# mainboard.net
KiCad netlist of a schematic drawn in EAGLE
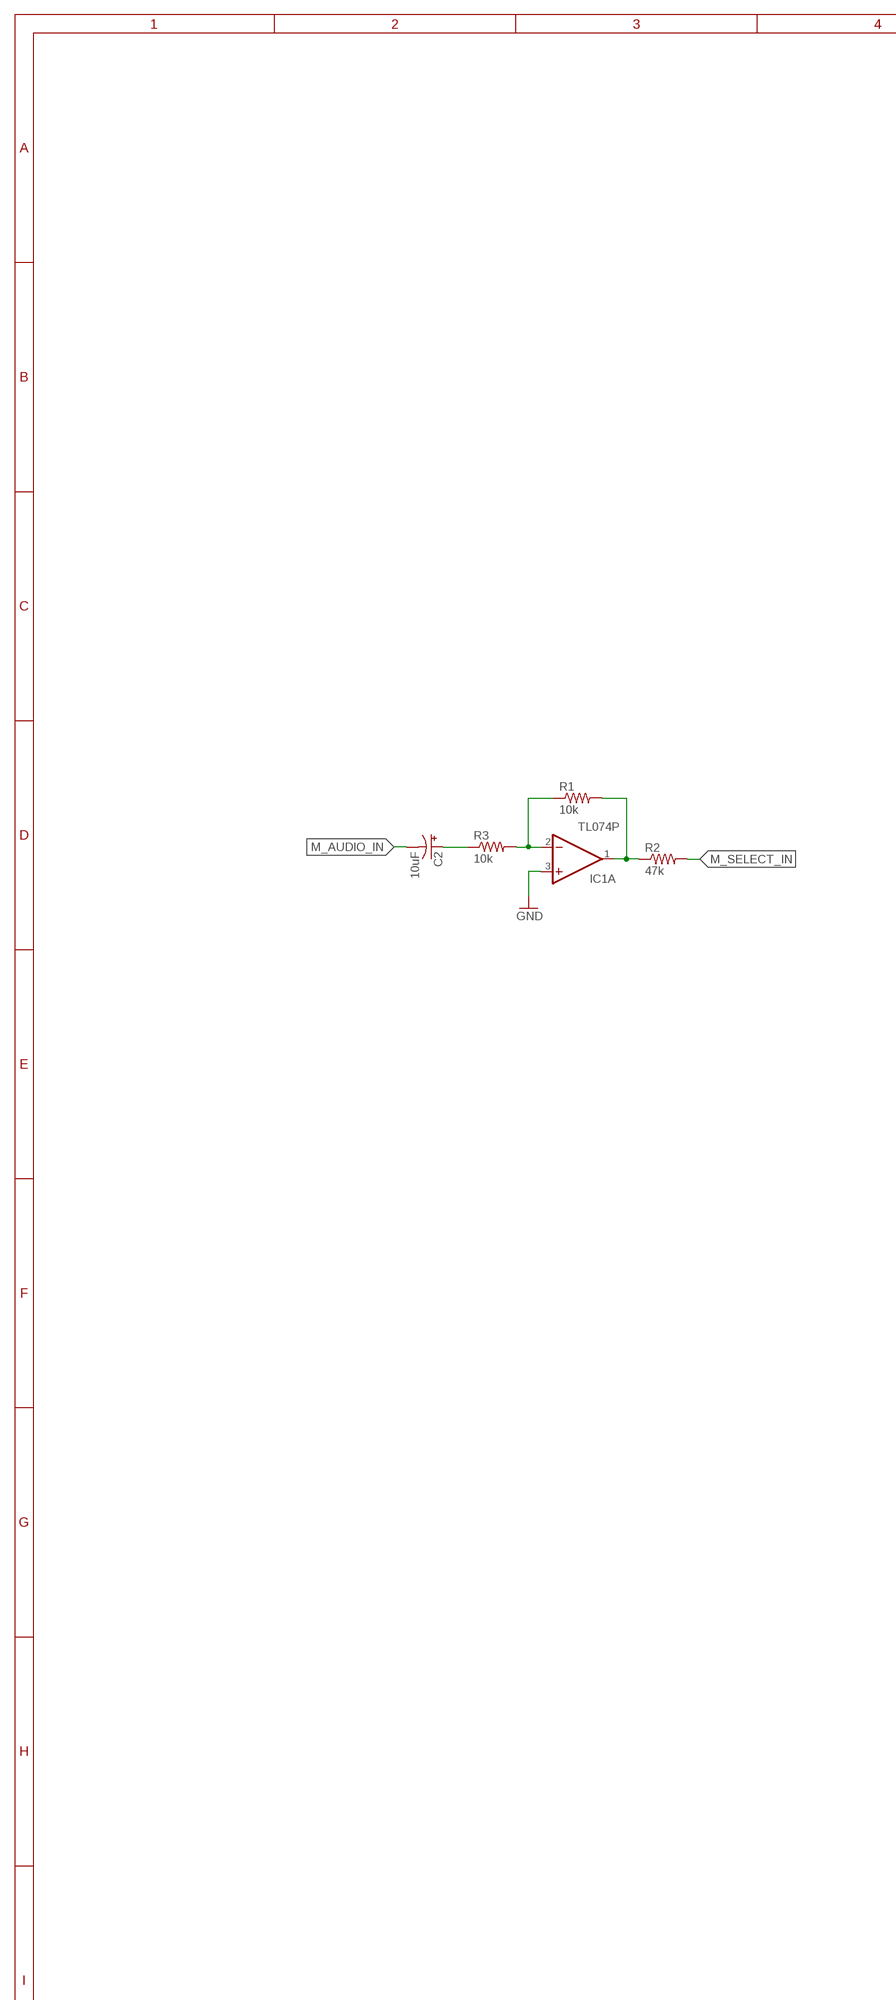
[diagram p0: schematic, sheet 1, part 1 of 2]
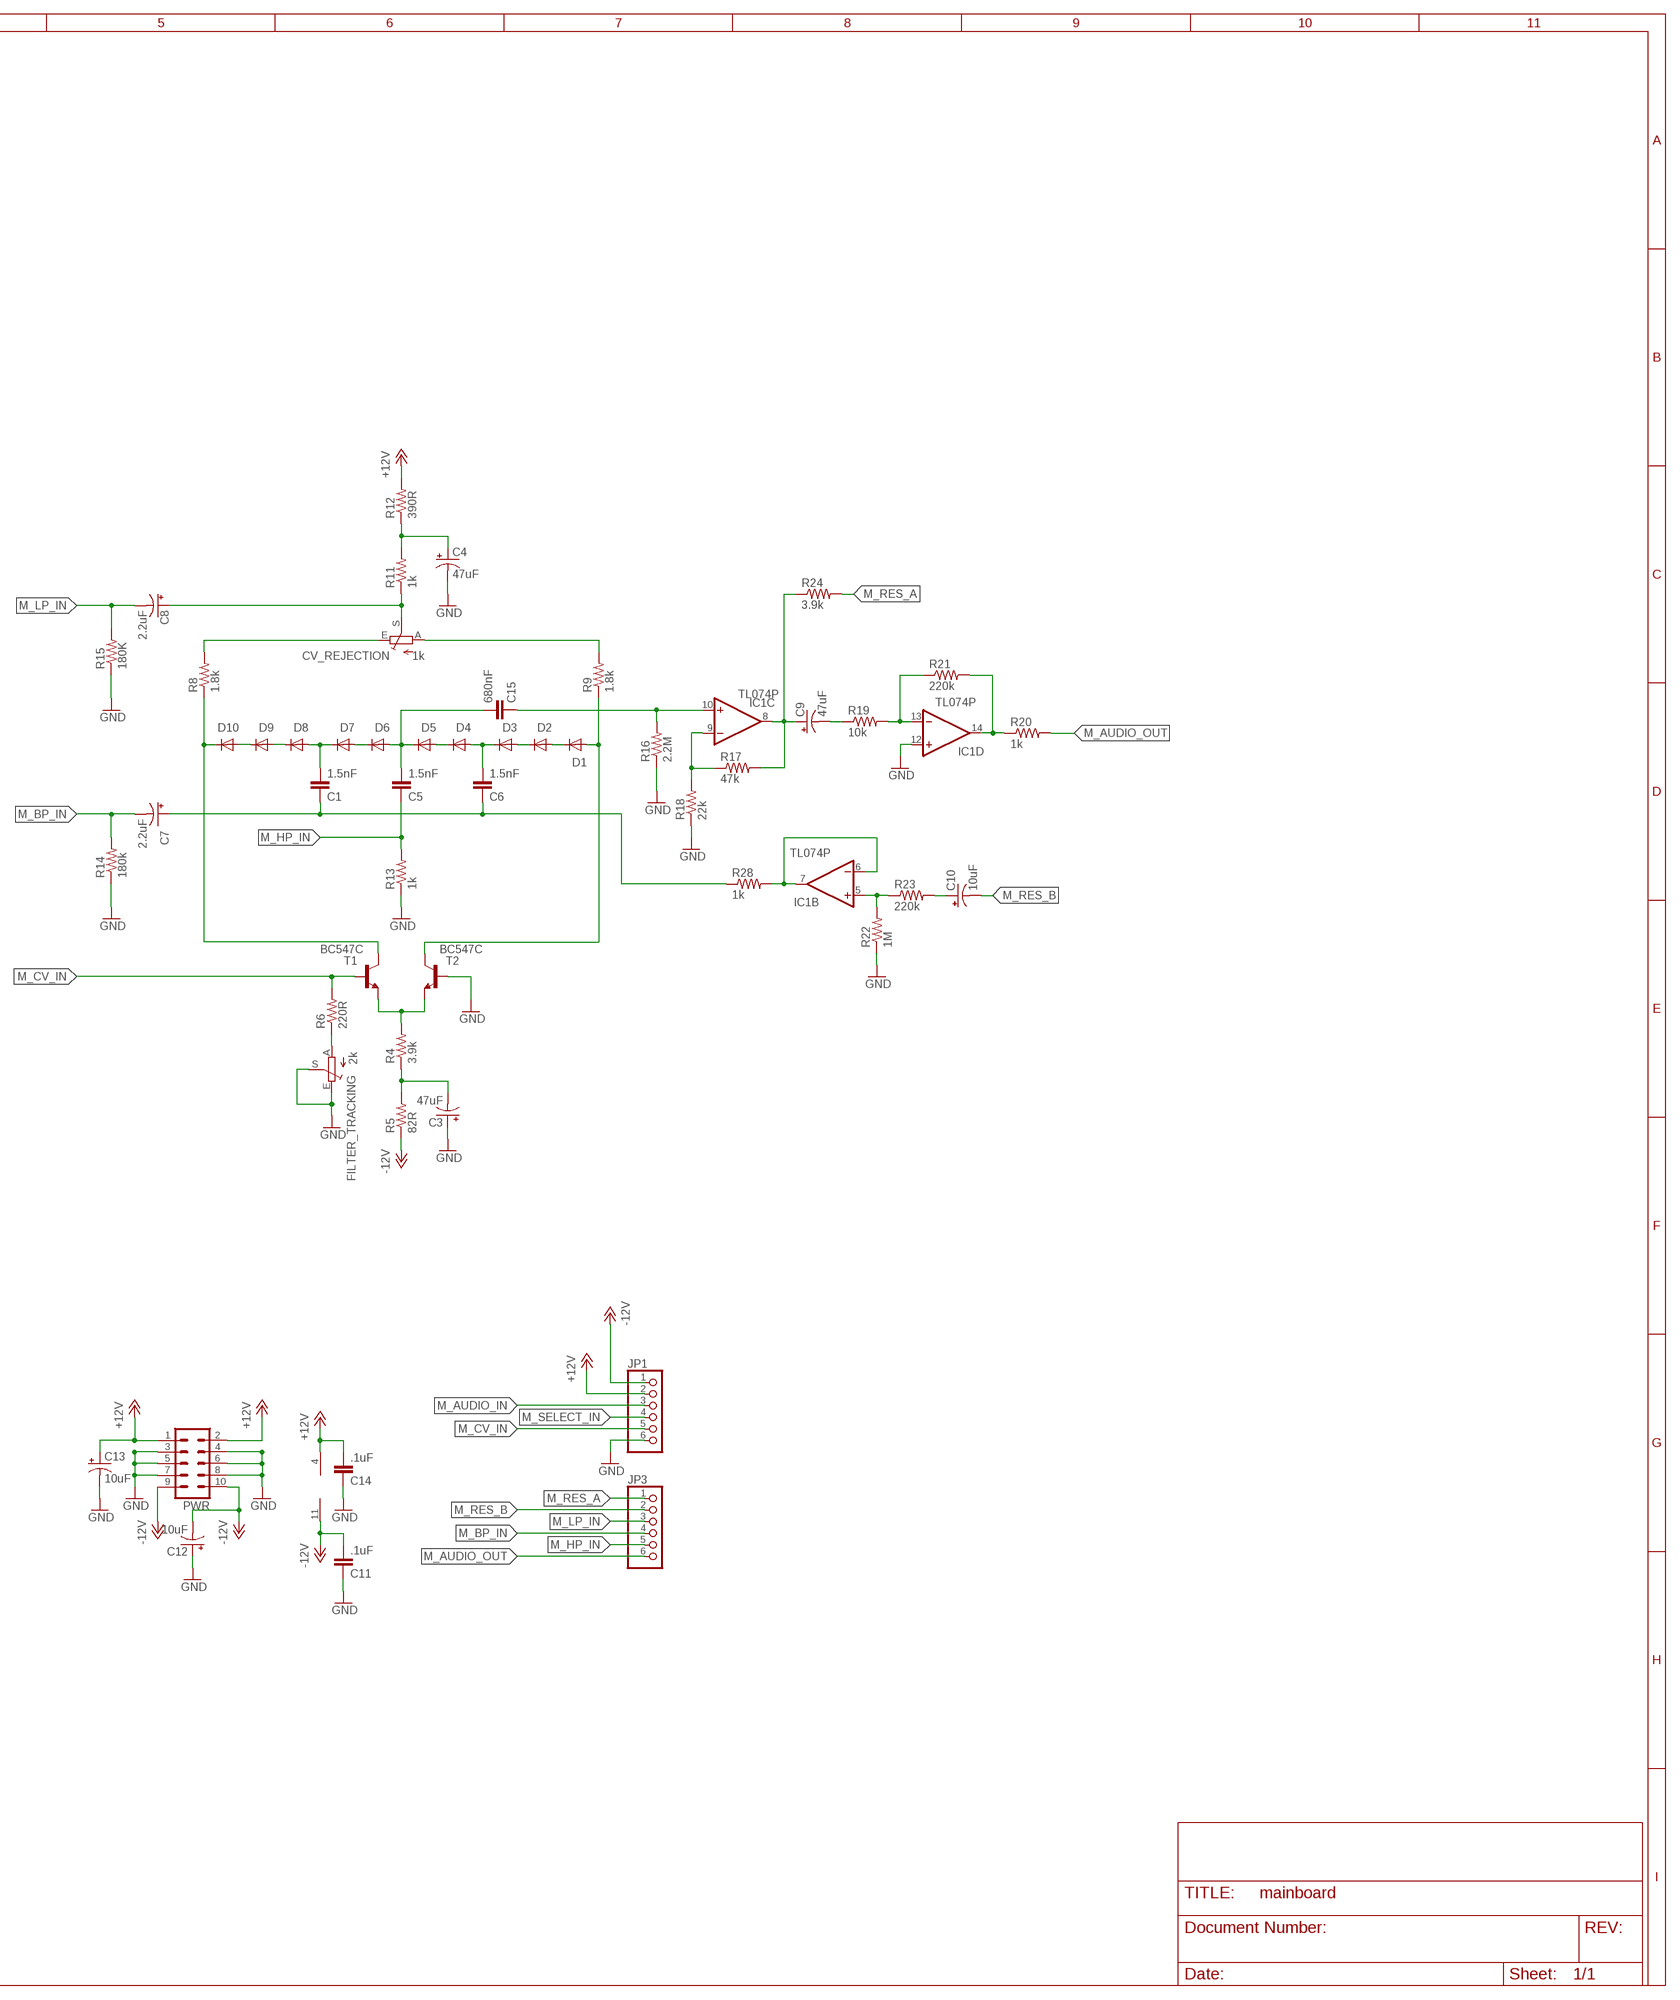
[diagram p1: schematic, sheet 1, part 2 of 2]

(export (version "E")
  (design (tool "Eeschema 10.0.6"))
  (components
    (comp (ref "C1")
      (value "1.5nF")
      (footprint "eagle-import:C050-024X044")
      (libsource (lib "eagle-import") (part "C-EU050-024X044"))
    )
    (comp (ref "C2")
      (value "10uF")
      (footprint "eagle-import:E2,5-5")
      (libsource (lib "eagle-import") (part "CPOL-USE2.5-5"))
    )
    (comp (ref "C3")
      (value "47uF")
      (footprint "eagle-import:E2,5-5")
      (libsource (lib "eagle-import") (part "CPOL-USE2.5-5"))
    )
    (comp (ref "C4")
      (value "47uF")
      (footprint "eagle-import:E2,5-5")
      (libsource (lib "eagle-import") (part "CPOL-USE2.5-5"))
    )
    (comp (ref "C5")
      (value "1.5nF")
      (footprint "eagle-import:C050-024X044")
      (libsource (lib "eagle-import") (part "C-EU050-024X044"))
    )
    (comp (ref "C6")
      (value "1.5nF")
      (footprint "eagle-import:C050-024X044")
      (libsource (lib "eagle-import") (part "C-EU050-024X044"))
    )
    (comp (ref "C7")
      (value "2.2uF")
      (footprint "eagle-import:E2,5-5")
      (libsource (lib "eagle-import") (part "CPOL-USE2.5-5"))
    )
    (comp (ref "C8")
      (value "2.2uF")
      (footprint "eagle-import:E2,5-5")
      (libsource (lib "eagle-import") (part "CPOL-USE2.5-5"))
    )
    (comp (ref "C9")
      (value "47uF")
      (footprint "eagle-import:E2,5-5")
      (libsource (lib "eagle-import") (part "CPOL-USE2.5-5"))
    )
    (comp (ref "C10")
      (value "10uF")
      (footprint "eagle-import:E2,5-5")
      (libsource (lib "eagle-import") (part "CPOL-USE2.5-5"))
    )
    (comp (ref "C11")
      (value ".1uF")
      (footprint "eagle-import:C050-024X044")
      (libsource (lib "eagle-import") (part "C-EU050-024X044"))
    )
    (comp (ref "C12")
      (value "10uF")
      (footprint "eagle-import:E2,5-5")
      (libsource (lib "eagle-import") (part "CPOL-USE2.5-5"))
    )
    (comp (ref "C13")
      (value "10uF")
      (footprint "eagle-import:E2,5-5")
      (libsource (lib "eagle-import") (part "CPOL-USE2.5-5"))
    )
    (comp (ref "C14")
      (value ".1uF")
      (footprint "eagle-import:C050-024X044")
      (libsource (lib "eagle-import") (part "C-EU050-024X044"))
    )
    (comp (ref "C15")
      (value "680nF")
      (footprint "eagle-import:C050-035X075")
      (libsource (lib "eagle-import") (part "resistor_348_C-EU050-035X075"))
    )
    (comp (ref "CV_REJECTION")
      (value "1k")
      (footprint "eagle-import:S64YW")
      (libsource (lib "eagle-import") (part "TRIM_1234-S64YW"))
    )
    (comp (ref "D1")
      (value "1N4148DO35-7")
      (footprint "eagle-import:DO35-7")
      (libsource (lib "eagle-import") (part "1N4148DO35-7"))
    )
    (comp (ref "D2")
      (value "1N4148DO35-7")
      (footprint "eagle-import:DO35-7")
      (libsource (lib "eagle-import") (part "1N4148DO35-7"))
    )
    (comp (ref "D3")
      (value "1N4148DO35-7")
      (footprint "eagle-import:DO35-7")
      (libsource (lib "eagle-import") (part "1N4148DO35-7"))
    )
    (comp (ref "D4")
      (value "1N4148DO35-7")
      (footprint "eagle-import:DO35-7")
      (libsource (lib "eagle-import") (part "1N4148DO35-7"))
    )
    (comp (ref "D5")
      (value "1N4148DO35-7")
      (footprint "eagle-import:DO35-7")
      (libsource (lib "eagle-import") (part "1N4148DO35-7"))
    )
    (comp (ref "D6")
      (value "1N4148DO35-7")
      (footprint "eagle-import:DO35-7")
      (libsource (lib "eagle-import") (part "1N4148DO35-7"))
    )
    (comp (ref "D7")
      (value "1N4148DO35-7")
      (footprint "eagle-import:DO35-7")
      (libsource (lib "eagle-import") (part "1N4148DO35-7"))
    )
    (comp (ref "D8")
      (value "1N4148DO35-7")
      (footprint "eagle-import:DO35-7")
      (libsource (lib "eagle-import") (part "1N4148DO35-7"))
    )
    (comp (ref "D9")
      (value "1N4148DO35-7")
      (footprint "eagle-import:DO35-7")
      (libsource (lib "eagle-import") (part "1N4148DO35-7"))
    )
    (comp (ref "D10")
      (value "1N4148DO35-7")
      (footprint "eagle-import:DO35-7")
      (libsource (lib "eagle-import") (part "1N4148DO35-7"))
    )
    (comp (ref "FILTER_TRACKING")
      (value "2k")
      (footprint "eagle-import:S64YW")
      (libsource (lib "eagle-import") (part "TRIM_1234-S64YW"))
    )
    (comp (ref "IC1")
      (value "TL074P")
      (footprint "eagle-import:DIL14")
      (libsource (lib "eagle-import") (part "TL074P"))
    )
    (comp (ref "JP1")
      (value "PINHD-1X6")
      (footprint "eagle-import:1X06")
      (libsource (lib "eagle-import") (part "PINHD-1X6"))
    )
    (comp (ref "JP3")
      (value "PINHD-1X6")
      (footprint "eagle-import:1X06")
      (libsource (lib "eagle-import") (part "PINHD-1X6"))
    )
    (comp (ref "PWR")
      (value "ML10")
      (footprint "eagle-import:ML10")
      (libsource (lib "eagle-import") (part "ML10"))
    )
    (comp (ref "R1")
      (value "10k")
      (footprint "eagle-import:0204_7")
      (libsource (lib "eagle-import") (part "R-US_0204/7"))
    )
    (comp (ref "R2")
      (value "47k")
      (footprint "eagle-import:0204_7")
      (libsource (lib "eagle-import") (part "R-US_0204/7"))
    )
    (comp (ref "R3")
      (value "10k")
      (footprint "eagle-import:0204_7")
      (libsource (lib "eagle-import") (part "R-US_0204/7"))
    )
    (comp (ref "R4")
      (value "3.9k")
      (footprint "eagle-import:0204_7")
      (libsource (lib "eagle-import") (part "R-US_0204/7"))
    )
    (comp (ref "R5")
      (value "82R")
      (footprint "eagle-import:0204_7")
      (libsource (lib "eagle-import") (part "R-US_0204/7"))
    )
    (comp (ref "R6")
      (value "220R")
      (footprint "eagle-import:0204_7")
      (libsource (lib "eagle-import") (part "R-US_0204/7"))
    )
    (comp (ref "R8")
      (value "1.8k")
      (footprint "eagle-import:0204_7")
      (libsource (lib "eagle-import") (part "R-US_0204/7"))
    )
    (comp (ref "R9")
      (value "1.8k")
      (footprint "eagle-import:0204_7")
      (libsource (lib "eagle-import") (part "R-US_0204/7"))
    )
    (comp (ref "R11")
      (value "1k")
      (footprint "eagle-import:0204_7")
      (libsource (lib "eagle-import") (part "R-US_0204/7"))
    )
    (comp (ref "R12")
      (value "390R")
      (footprint "eagle-import:0204_7")
      (libsource (lib "eagle-import") (part "R-US_0204/7"))
    )
    (comp (ref "R13")
      (value "1k")
      (footprint "eagle-import:0204_7")
      (libsource (lib "eagle-import") (part "R-US_0204/7"))
    )
    (comp (ref "R14")
      (value "180k")
      (footprint "eagle-import:0204_7")
      (libsource (lib "eagle-import") (part "R-US_0204/7"))
    )
    (comp (ref "R15")
      (value "180K")
      (footprint "eagle-import:0204_7")
      (libsource (lib "eagle-import") (part "R-US_0204/7"))
    )
    (comp (ref "R16")
      (value "2.2M")
      (footprint "eagle-import:0204_7")
      (libsource (lib "eagle-import") (part "R-US_0204/7"))
    )
    (comp (ref "R17")
      (value "47k")
      (footprint "eagle-import:0204_7")
      (libsource (lib "eagle-import") (part "R-US_0204/7"))
    )
    (comp (ref "R18")
      (value "22k")
      (footprint "eagle-import:0204_7")
      (libsource (lib "eagle-import") (part "R-US_0204/7"))
    )
    (comp (ref "R19")
      (value "10k")
      (footprint "eagle-import:0204_7")
      (libsource (lib "eagle-import") (part "R-US_0204/7"))
    )
    (comp (ref "R20")
      (value "1k")
      (footprint "eagle-import:0204_7")
      (libsource (lib "eagle-import") (part "R-US_0204/7"))
    )
    (comp (ref "R21")
      (value "220k")
      (footprint "eagle-import:0204_7")
      (libsource (lib "eagle-import") (part "R-US_0204/7"))
    )
    (comp (ref "R22")
      (value "1M")
      (footprint "eagle-import:0204_7")
      (libsource (lib "eagle-import") (part "R-US_0204/7"))
    )
    (comp (ref "R23")
      (value "220k")
      (footprint "eagle-import:0204_7")
      (libsource (lib "eagle-import") (part "R-US_0204/7"))
    )
    (comp (ref "R24")
      (value "3.9k")
      (footprint "eagle-import:0204_7")
      (libsource (lib "eagle-import") (part "R-US_0204/7"))
    )
    (comp (ref "R28")
      (value "1k")
      (footprint "eagle-import:0204_7")
      (libsource (lib "eagle-import") (part "R-US_0204/7"))
    )
    (comp (ref "T1")
      (value "BC547C")
      (footprint "eagle-import:TO92-CBE")
      (libsource (lib "eagle-import") (part "-NPN-TO92-CBEBC547"))
    )
    (comp (ref "T2")
      (value "BC547C")
      (footprint "eagle-import:TO92-CBE")
      (libsource (lib "eagle-import") (part "-NPN-TO92-CBEBC547"))
    )
  )
  (nets
    (net (code "1") (name "+12V") (class "Default")
      (node (ref "C13") (pin "+") (pinfunction "+_+") (pintype "passive"))
      (node (ref "C14") (pin "1") (pinfunction "1_1") (pintype "passive"))
      (node (ref "IC1") (pin "4") (pinfunction "V+_4") (pintype "power_in"))
      (node (ref "JP1") (pin "2") (pinfunction "2_2") (pintype "passive"))
      (node (ref "PWR") (pin "1") (pinfunction "1_1") (pintype "passive"))
      (node (ref "PWR") (pin "2") (pinfunction "2_2") (pintype "passive"))
      (node (ref "R12") (pin "2") (pinfunction "2_2") (pintype "passive"))
    )
    (net (code "2") (name "-12V") (class "Default")
      (node (ref "C11") (pin "1") (pinfunction "1_1") (pintype "passive"))
      (node (ref "C12") (pin "-") (pinfunction "-_-") (pintype "passive"))
      (node (ref "IC1") (pin "11") (pinfunction "V-_11") (pintype "power_in"))
      (node (ref "JP1") (pin "1") (pinfunction "1_1") (pintype "passive"))
      (node (ref "PWR") (pin "10") (pinfunction "10_10") (pintype "passive"))
      (node (ref "PWR") (pin "9") (pinfunction "9_9") (pintype "passive"))
      (node (ref "R5") (pin "1") (pinfunction "1_1") (pintype "passive"))
    )
    (net (code "3") (name "GND") (class "Default")
      (node (ref "C11") (pin "2") (pinfunction "2_2") (pintype "passive"))
      (node (ref "C12") (pin "+") (pinfunction "+_+") (pintype "passive"))
      (node (ref "C13") (pin "-") (pinfunction "-_-") (pintype "passive"))
      (node (ref "C14") (pin "2") (pinfunction "2_2") (pintype "passive"))
      (node (ref "C3") (pin "+") (pinfunction "+_+") (pintype "passive"))
      (node (ref "C4") (pin "-") (pinfunction "-_-") (pintype "passive"))
      (node (ref "FILTER_TRACKING") (pin "E") (pinfunction "E_E") (pintype "passive"))
      (node (ref "FILTER_TRACKING") (pin "S") (pinfunction "S_S") (pintype "passive"))
      (node (ref "IC1") (pin "12") (pinfunction "+IN_12") (pintype "input"))
      (node (ref "IC1") (pin "3") (pinfunction "+IN_3") (pintype "input"))
      (node (ref "JP1") (pin "6") (pinfunction "6_6") (pintype "passive"))
      (node (ref "PWR") (pin "3") (pinfunction "3_3") (pintype "passive"))
      (node (ref "PWR") (pin "4") (pinfunction "4_4") (pintype "passive"))
      (node (ref "PWR") (pin "5") (pinfunction "5_5") (pintype "passive"))
      (node (ref "PWR") (pin "6") (pinfunction "6_6") (pintype "passive"))
      (node (ref "PWR") (pin "7") (pinfunction "7_7") (pintype "passive"))
      (node (ref "PWR") (pin "8") (pinfunction "8_8") (pintype "passive"))
      (node (ref "R13") (pin "1") (pinfunction "1_1") (pintype "passive"))
      (node (ref "R14") (pin "1") (pinfunction "1_1") (pintype "passive"))
      (node (ref "R15") (pin "1") (pinfunction "1_1") (pintype "passive"))
      (node (ref "R16") (pin "1") (pinfunction "1_1") (pintype "passive"))
      (node (ref "R18") (pin "1") (pinfunction "1_1") (pintype "passive"))
      (node (ref "R22") (pin "1") (pinfunction "1_1") (pintype "passive"))
      (node (ref "T2") (pin "B") (pinfunction "B_B") (pintype "passive"))
    )
    (net (code "4") (name "M_AUDIO_IN") (class "Default")
      (node (ref "C2") (pin "-") (pinfunction "-_-") (pintype "passive"))
      (node (ref "JP1") (pin "3") (pinfunction "3_3") (pintype "passive"))
    )
    (net (code "5") (name "M_AUDIO_OUT") (class "Default")
      (node (ref "JP3") (pin "6") (pinfunction "6_6") (pintype "passive"))
      (node (ref "R20") (pin "2") (pinfunction "2_2") (pintype "passive"))
    )
    (net (code "6") (name "M_BP_IN") (class "Default")
      (node (ref "C7") (pin "-") (pinfunction "-_-") (pintype "passive"))
      (node (ref "JP3") (pin "4") (pinfunction "4_4") (pintype "passive"))
      (node (ref "R14") (pin "2") (pinfunction "2_2") (pintype "passive"))
    )
    (net (code "7") (name "M_CV_IN") (class "Default")
      (node (ref "JP1") (pin "5") (pinfunction "5_5") (pintype "passive"))
      (node (ref "R6") (pin "2") (pinfunction "2_2") (pintype "passive"))
      (node (ref "T1") (pin "B") (pinfunction "B_B") (pintype "passive"))
    )
    (net (code "8") (name "M_HP_IN") (class "Default")
      (node (ref "C5") (pin "2") (pinfunction "2_2") (pintype "passive"))
      (node (ref "JP3") (pin "5") (pinfunction "5_5") (pintype "passive"))
      (node (ref "R13") (pin "2") (pinfunction "2_2") (pintype "passive"))
    )
    (net (code "9") (name "M_LP_IN") (class "Default")
      (node (ref "C8") (pin "-") (pinfunction "-_-") (pintype "passive"))
      (node (ref "JP3") (pin "3") (pinfunction "3_3") (pintype "passive"))
      (node (ref "R15") (pin "2") (pinfunction "2_2") (pintype "passive"))
    )
    (net (code "10") (name "M_RES_A") (class "Default")
      (node (ref "JP3") (pin "1") (pinfunction "1_1") (pintype "passive"))
      (node (ref "R24") (pin "2") (pinfunction "2_2") (pintype "passive"))
    )
    (net (code "11") (name "M_RES_B") (class "Default")
      (node (ref "C10") (pin "-") (pinfunction "-_-") (pintype "passive"))
      (node (ref "JP3") (pin "2") (pinfunction "2_2") (pintype "passive"))
    )
    (net (code "12") (name "M_SELECT_IN") (class "Default")
      (node (ref "JP1") (pin "4") (pinfunction "4_4") (pintype "passive"))
      (node (ref "R2") (pin "2") (pinfunction "2_2") (pintype "passive"))
    )
    (net (code "13") (name "Net-(C1-Pad1)") (class "Default")
      (node (ref "C1") (pin "1") (pinfunction "1_1") (pintype "passive"))
      (node (ref "D7") (pin "C") (pinfunction "C_C") (pintype "passive"))
      (node (ref "D8") (pin "A") (pinfunction "A_A") (pintype "passive"))
    )
    (net (code "14") (name "Net-(C1-Pad2)") (class "Default")
      (node (ref "C1") (pin "2") (pinfunction "2_2") (pintype "passive"))
      (node (ref "C6") (pin "2") (pinfunction "2_2") (pintype "passive"))
      (node (ref "C7") (pin "+") (pinfunction "+_+") (pintype "passive"))
      (node (ref "R28") (pin "1") (pinfunction "1_1") (pintype "passive"))
    )
    (net (code "15") (name "Net-(C2-Pad+)") (class "Default")
      (node (ref "C2") (pin "+") (pinfunction "+_+") (pintype "passive"))
      (node (ref "R3") (pin "1") (pinfunction "1_1") (pintype "passive"))
    )
    (net (code "16") (name "Net-(C3-Pad-)") (class "Default")
      (node (ref "C3") (pin "-") (pinfunction "-_-") (pintype "passive"))
      (node (ref "R4") (pin "1") (pinfunction "1_1") (pintype "passive"))
      (node (ref "R5") (pin "2") (pinfunction "2_2") (pintype "passive"))
    )
    (net (code "17") (name "Net-(C4-Pad+)") (class "Default")
      (node (ref "C4") (pin "+") (pinfunction "+_+") (pintype "passive"))
      (node (ref "R11") (pin "2") (pinfunction "2_2") (pintype "passive"))
      (node (ref "R12") (pin "1") (pinfunction "1_1") (pintype "passive"))
    )
    (net (code "18") (name "Net-(C6-Pad1)") (class "Default")
      (node (ref "C6") (pin "1") (pinfunction "1_1") (pintype "passive"))
      (node (ref "D3") (pin "C") (pinfunction "C_C") (pintype "passive"))
      (node (ref "D4") (pin "A") (pinfunction "A_A") (pintype "passive"))
    )
    (net (code "19") (name "Net-(C8-Pad+)") (class "Default")
      (node (ref "C8") (pin "+") (pinfunction "+_+") (pintype "passive"))
      (node (ref "CV_REJECTION") (pin "S") (pinfunction "S_S") (pintype "passive"))
      (node (ref "R11") (pin "1") (pinfunction "1_1") (pintype "passive"))
    )
    (net (code "20") (name "Net-(C9-Pad-)") (class "Default")
      (node (ref "C9") (pin "-") (pinfunction "-_-") (pintype "passive"))
      (node (ref "R19") (pin "1") (pinfunction "1_1") (pintype "passive"))
    )
    (net (code "21") (name "Net-(C10-Pad+)") (class "Default")
      (node (ref "C10") (pin "+") (pinfunction "+_+") (pintype "passive"))
      (node (ref "R23") (pin "2") (pinfunction "2_2") (pintype "passive"))
    )
    (net (code "22") (name "Net-(C15-Pad1)") (class "Default")
      (node (ref "C15") (pin "1") (pinfunction "1_1") (pintype "passive"))
      (node (ref "C5") (pin "1") (pinfunction "1_1") (pintype "passive"))
      (node (ref "D5") (pin "C") (pinfunction "C_C") (pintype "passive"))
      (node (ref "D6") (pin "A") (pinfunction "A_A") (pintype "passive"))
    )
    (net (code "23") (name "Net-(CV_REJECTION-PadA)") (class "Default")
      (node (ref "CV_REJECTION") (pin "A") (pinfunction "A_A") (pintype "passive"))
      (node (ref "R9") (pin "2") (pinfunction "2_2") (pintype "passive"))
    )
    (net (code "24") (name "Net-(CV_REJECTION-PadE)") (class "Default")
      (node (ref "CV_REJECTION") (pin "E") (pinfunction "E_E") (pintype "passive"))
      (node (ref "R8") (pin "2") (pinfunction "2_2") (pintype "passive"))
    )
    (net (code "25") (name "Net-(D1-PadA)") (class "Default")
      (node (ref "D1") (pin "A") (pinfunction "A_A") (pintype "passive"))
      (node (ref "R9") (pin "1") (pinfunction "1_1") (pintype "passive"))
      (node (ref "T2") (pin "C") (pinfunction "C_C") (pintype "passive"))
    )
    (net (code "26") (name "Net-(D1-PadC)") (class "Default")
      (node (ref "D1") (pin "C") (pinfunction "C_C") (pintype "passive"))
      (node (ref "D2") (pin "A") (pinfunction "A_A") (pintype "passive"))
    )
    (net (code "27") (name "Net-(D2-PadC)") (class "Default")
      (node (ref "D2") (pin "C") (pinfunction "C_C") (pintype "passive"))
      (node (ref "D3") (pin "A") (pinfunction "A_A") (pintype "passive"))
    )
    (net (code "28") (name "Net-(D4-PadC)") (class "Default")
      (node (ref "D4") (pin "C") (pinfunction "C_C") (pintype "passive"))
      (node (ref "D5") (pin "A") (pinfunction "A_A") (pintype "passive"))
    )
    (net (code "29") (name "Net-(D6-PadC)") (class "Default")
      (node (ref "D6") (pin "C") (pinfunction "C_C") (pintype "passive"))
      (node (ref "D7") (pin "A") (pinfunction "A_A") (pintype "passive"))
    )
    (net (code "30") (name "Net-(D8-PadC)") (class "Default")
      (node (ref "D8") (pin "C") (pinfunction "C_C") (pintype "passive"))
      (node (ref "D9") (pin "A") (pinfunction "A_A") (pintype "passive"))
    )
    (net (code "31") (name "Net-(D10-PadA)") (class "Default")
      (node (ref "D10") (pin "A") (pinfunction "A_A") (pintype "passive"))
      (node (ref "D9") (pin "C") (pinfunction "C_C") (pintype "passive"))
    )
    (net (code "32") (name "Net-(D10-PadC)") (class "Default")
      (node (ref "D10") (pin "C") (pinfunction "C_C") (pintype "passive"))
      (node (ref "R8") (pin "1") (pinfunction "1_1") (pintype "passive"))
      (node (ref "T1") (pin "C") (pinfunction "C_C") (pintype "passive"))
    )
    (net (code "33") (name "Net-(FILTER_TRACKING-PadA)") (class "Default")
      (node (ref "FILTER_TRACKING") (pin "A") (pinfunction "A_A") (pintype "passive"))
      (node (ref "R6") (pin "1") (pinfunction "1_1") (pintype "passive"))
    )
    (net (code "34") (name "Net-(IC1A--IN)") (class "Default")
      (node (ref "IC1") (pin "2") (pinfunction "-IN_2") (pintype "input"))
      (node (ref "R1") (pin "1") (pinfunction "1_1") (pintype "passive"))
      (node (ref "R3") (pin "2") (pinfunction "2_2") (pintype "passive"))
    )
    (net (code "35") (name "Net-(IC1A-OUT)") (class "Default")
      (node (ref "IC1") (pin "1") (pinfunction "OUT_1") (pintype "output"))
      (node (ref "R1") (pin "2") (pinfunction "2_2") (pintype "passive"))
      (node (ref "R2") (pin "1") (pinfunction "1_1") (pintype "passive"))
    )
    (net (code "36") (name "Net-(IC1B-+IN)") (class "Default")
      (node (ref "IC1") (pin "5") (pinfunction "+IN_5") (pintype "input"))
      (node (ref "R22") (pin "2") (pinfunction "2_2") (pintype "passive"))
      (node (ref "R23") (pin "1") (pinfunction "1_1") (pintype "passive"))
    )
    (net (code "37") (name "Net-(IC1B--IN)") (class "Default")
      (node (ref "IC1") (pin "6") (pinfunction "-IN_6") (pintype "input"))
      (node (ref "IC1") (pin "7") (pinfunction "OUT_7") (pintype "output"))
      (node (ref "R28") (pin "2") (pinfunction "2_2") (pintype "passive"))
    )
    (net (code "38") (name "Net-(IC1C-+IN)") (class "Default")
      (node (ref "C15") (pin "2") (pinfunction "2_2") (pintype "passive"))
      (node (ref "IC1") (pin "10") (pinfunction "+IN_10") (pintype "input"))
      (node (ref "R16") (pin "2") (pinfunction "2_2") (pintype "passive"))
    )
    (net (code "39") (name "Net-(IC1C--IN)") (class "Default")
      (node (ref "IC1") (pin "9") (pinfunction "-IN_9") (pintype "input"))
      (node (ref "R17") (pin "1") (pinfunction "1_1") (pintype "passive"))
      (node (ref "R18") (pin "2") (pinfunction "2_2") (pintype "passive"))
    )
    (net (code "40") (name "Net-(IC1C-OUT)") (class "Default")
      (node (ref "C9") (pin "+") (pinfunction "+_+") (pintype "passive"))
      (node (ref "IC1") (pin "8") (pinfunction "OUT_8") (pintype "output"))
      (node (ref "R17") (pin "2") (pinfunction "2_2") (pintype "passive"))
      (node (ref "R24") (pin "1") (pinfunction "1_1") (pintype "passive"))
    )
    (net (code "41") (name "Net-(IC1D--IN)") (class "Default")
      (node (ref "IC1") (pin "13") (pinfunction "-IN_13") (pintype "input"))
      (node (ref "R19") (pin "2") (pinfunction "2_2") (pintype "passive"))
      (node (ref "R21") (pin "1") (pinfunction "1_1") (pintype "passive"))
    )
    (net (code "42") (name "Net-(IC1D-OUT)") (class "Default")
      (node (ref "IC1") (pin "14") (pinfunction "OUT_14") (pintype "output"))
      (node (ref "R20") (pin "1") (pinfunction "1_1") (pintype "passive"))
      (node (ref "R21") (pin "2") (pinfunction "2_2") (pintype "passive"))
    )
    (net (code "43") (name "Net-(R4-Pad2)") (class "Default")
      (node (ref "R4") (pin "2") (pinfunction "2_2") (pintype "passive"))
      (node (ref "T1") (pin "E") (pinfunction "E_E") (pintype "passive"))
      (node (ref "T2") (pin "E") (pinfunction "E_E") (pintype "passive"))
    )
    (net (code "44") (name "unconnected-(CV_REJECTION-S-PadS@1)") (class "Default")
      (node (ref "CV_REJECTION") (pin "S@1") (pinfunction "S_S@1") (pintype "passive"))
    )
    (net (code "45") (name "unconnected-(FILTER_TRACKING-S-PadS@1)") (class "Default")
      (node (ref "FILTER_TRACKING") (pin "S@1") (pinfunction "S_S@1") (pintype "passive"))
    )
  )
)
